# MCU_PFC161.net
KiCad netlist of a schematic drawn in Altium Designer
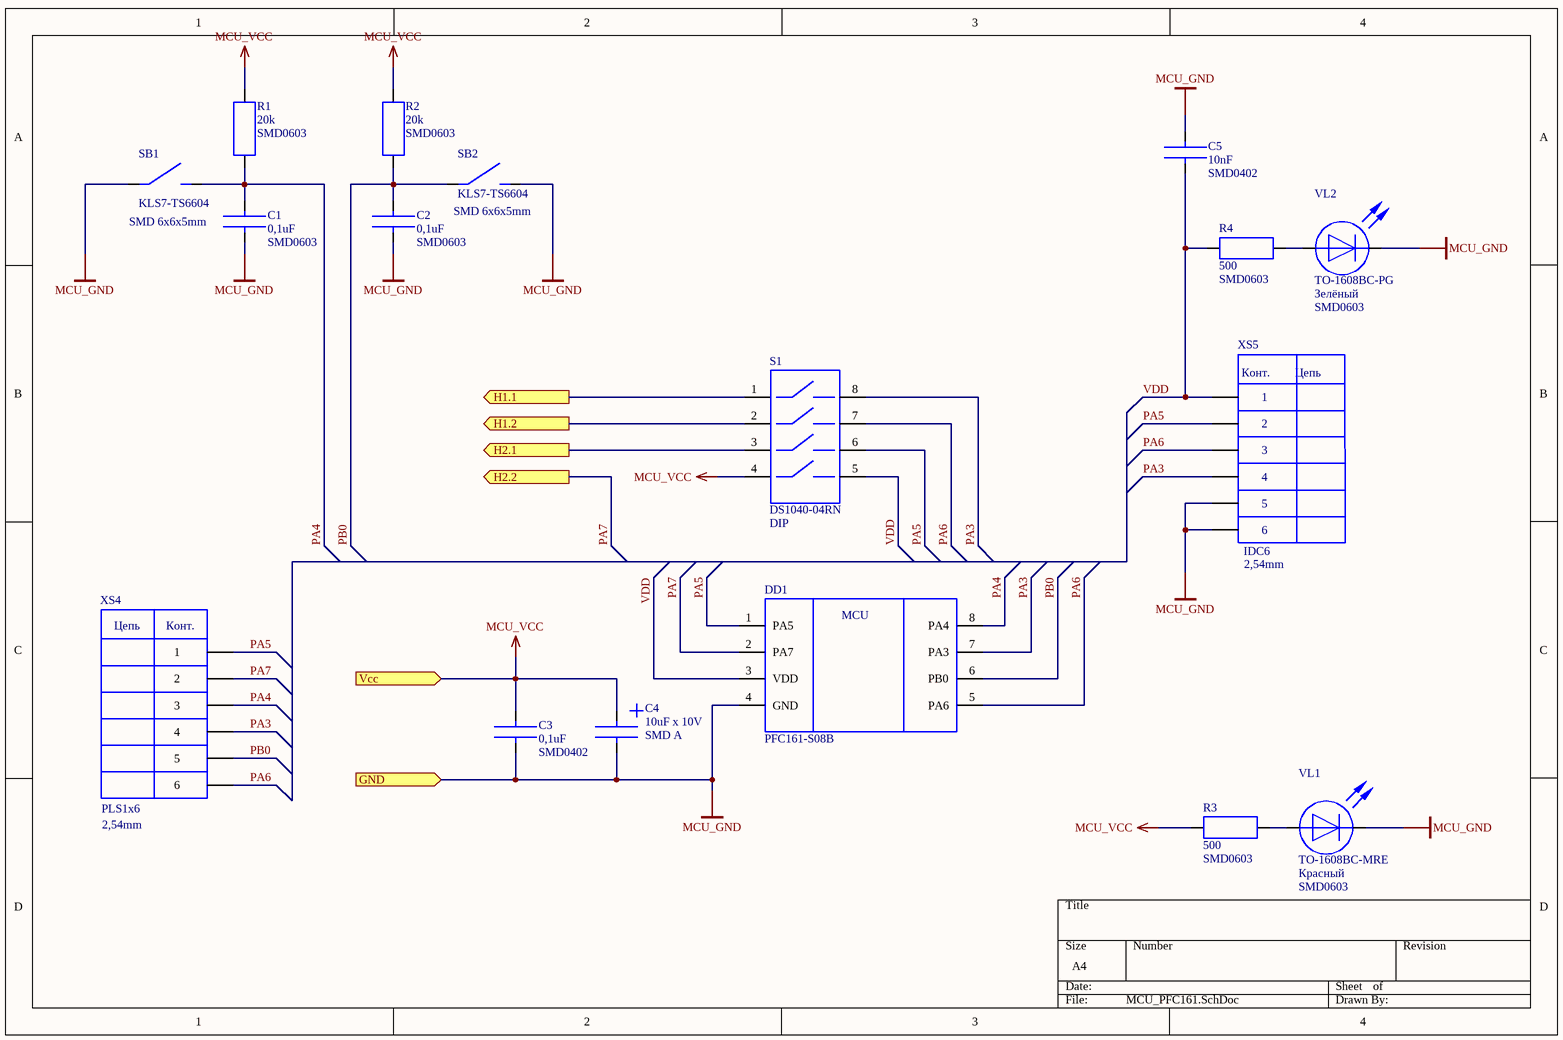
[diagram p0: MCU_PFC161.SchDoc]

(export (version "E")
  (design (tool "Eeschema 10.0.6"))
  (components
    (comp (ref "C1")
      (value "0,1uF")
      (footprint "SMD0603(1005)")
      (fields (field (name "PACKAGE") "SMD0603"))
      (libsource (lib "MechanikLibrary") (part "CER_CUP_0603"))
    )
    (comp (ref "C2")
      (value "0,1uF")
      (footprint "SMD0603(1005)")
      (fields (field (name "PACKAGE") "SMD0603"))
      (libsource (lib "MechanikLibrary") (part "CER_CUP_0603"))
    )
    (comp (ref "C3")
      (value "0,1uF")
      (footprint "SMD0402(1608)")
      (fields (field (name "PACKAGE") "SMD0402"))
      (libsource (lib "MechanikLibrary") (part "CER_CUP_0402"))
    )
    (comp (ref "C4")
      (value "10uF x 10V")
      (footprint "TANT_CAP_A(3216)")
      (fields (field (name "PACKAGE") "SMD A"))
      (libsource (lib "MechanikLibrary") (part "C_TANT_A"))
    )
    (comp (ref "C5")
      (value "10nF")
      (footprint "SMD0603(1005)")
      (fields (field (name "PACKAGE") "SMD0402"))
      (libsource (lib "MechanikLibrary") (part "CER_CUP_0402"))
    )
    (comp (ref "DD1")
      (value "PFC161-S08B")
      (footprint "SOIC8")
      (libsource (lib "MechanikLibrary") (part "PFC161-S08B"))
    )
    (comp (ref "R1")
      (value "20k")
      (footprint "SMD0603(1005)")
      (fields (field (name "PACKAGE") "SMD0603"))
      (libsource (lib "MechanikLibrary") (part "R_0603"))
    )
    (comp (ref "R2")
      (value "20k")
      (footprint "SMD0603(1005)")
      (fields (field (name "PACKAGE") "SMD0603"))
      (libsource (lib "MechanikLibrary") (part "R_0603"))
    )
    (comp (ref "R3")
      (value "500")
      (footprint "SMD0603(1005)")
      (fields (field (name "PACKAGE") "SMD0603"))
      (libsource (lib "MechanikLibrary") (part "R_0603"))
    )
    (comp (ref "R4")
      (value "500")
      (footprint "SMD0603(1005)")
      (fields (field (name "PACKAGE") "SMD0603"))
      (libsource (lib "MechanikLibrary") (part "R_0603"))
    )
    (comp (ref "S1")
      (value "DS1040-04RN")
      (footprint "DIP_SWITCH_4_2.54")
      (fields (field (name "PACKAGE") "DIP"))
      (libsource (lib "MechanikLibrary") (part "Переключатель DIP DS1040-04RN"))
    )
    (comp (ref "SB1")
      (value "KLS7-TS6604")
      (footprint "KLS7-TS6604 (IT-1102SA)")
      (fields (field (name "PACKAGE") "SMD 6х6х5mm"))
      (libsource (lib "MechanikLibrary") (part "Кнопка KLS7-TS6604 (IT-1102SA)"))
    )
    (comp (ref "SB2")
      (value "KLS7-TS6604")
      (footprint "KLS7-TS6604 (IT-1102SA)")
      (fields (field (name "PACKAGE") "SMD 6х6х5mm"))
      (libsource (lib "MechanikLibrary") (part "Кнопка KLS7-TS6604 (IT-1102SA)"))
    )
    (comp (ref "VL1")
      (value "TO-1608BC-MRE")
      (footprint "LED_SMD0603(1005)")
      (fields (field (name "LIGHT") "Красный") (field (name "PACKAGE") "SMD0603"))
      (libsource (lib "MechanikLibrary") (part "LED_0603"))
    )
    (comp (ref "VL2")
      (value "TO-1608BC-PG")
      (footprint "LED_SMD0603(1005)")
      (fields (field (name "LIGHT") "Зелёный") (field (name "PACKAGE") "SMD0603"))
      (libsource (lib "MechanikLibrary") (part "LED_0603"))
    )
    (comp (ref "XS4")
      (value "PLS1x6")
      (footprint "PLS1x6")
      (fields (field (name "PACKAGE") "2,54mm"))
      (libsource (lib "MechanikLibrary") (part "PLS1x6"))
    )
    (comp (ref "XS5")
      (value "IDC6")
      (footprint "IDC-6 (2.54)")
      (fields (field (name "PACKAGE") "2,54mm"))
      (libsource (lib "MechanikLibrary") (part "IDC6"))
    )
  )
  (nets
    (net (code "1") (name "/H1.1") (class "Default")
      (node (ref "S1") (pin "1") (pinfunction "1_1") (pintype "passive"))
    )
    (net (code "2") (name "/H1.2") (class "Default")
      (node (ref "S1") (pin "2") (pinfunction "2_2") (pintype "passive"))
    )
    (net (code "3") (name "/H2.1") (class "Default")
      (node (ref "S1") (pin "3") (pinfunction "3_3") (pintype "passive"))
    )
    (net (code "4") (name "/PA3") (class "Default")
      (node (ref "DD1") (pin "7") (pinfunction "PA3_7") (pintype "passive"))
      (node (ref "S1") (pin "8") (pinfunction "1_8") (pintype "passive"))
      (node (ref "XS4") (pin "4") (pinfunction "4_4") (pintype "passive"))
      (node (ref "XS5") (pin "4") (pintype "passive"))
    )
    (net (code "5") (name "/PA4") (class "Default")
      (node (ref "C1") (pin "2") (pintype "passive"))
      (node (ref "DD1") (pin "8") (pinfunction "PA4_8") (pintype "passive"))
      (node (ref "R1") (pin "1") (pintype "passive"))
      (node (ref "SB1") (pin "2") (pintype "passive"))
      (node (ref "XS4") (pin "3") (pinfunction "3_3") (pintype "passive"))
    )
    (net (code "6") (name "/PA5") (class "Default")
      (node (ref "DD1") (pin "1") (pinfunction "PA5_1") (pintype "passive"))
      (node (ref "S1") (pin "6") (pinfunction "3_6") (pintype "passive"))
      (node (ref "XS4") (pin "1") (pinfunction "1_1") (pintype "passive"))
      (node (ref "XS5") (pin "2") (pintype "passive"))
    )
    (net (code "7") (name "/PA6") (class "Default")
      (node (ref "DD1") (pin "5") (pinfunction "PA6_5") (pintype "passive"))
      (node (ref "S1") (pin "7") (pinfunction "2_7") (pintype "passive"))
      (node (ref "XS4") (pin "6") (pinfunction "6_6") (pintype "passive"))
      (node (ref "XS5") (pin "3") (pintype "passive"))
    )
    (net (code "8") (name "/PA7") (class "Default")
      (node (ref "DD1") (pin "2") (pinfunction "PA7_2") (pintype "passive"))
      (node (ref "XS4") (pin "2") (pinfunction "2_2") (pintype "passive"))
    )
    (net (code "9") (name "/PB0") (class "Default")
      (node (ref "C2") (pin "2") (pintype "passive"))
      (node (ref "DD1") (pin "6") (pinfunction "PB0_6") (pintype "passive"))
      (node (ref "R2") (pin "1") (pintype "passive"))
      (node (ref "SB2") (pin "1") (pintype "passive"))
      (node (ref "XS4") (pin "5") (pinfunction "5_5") (pintype "passive"))
    )
    (net (code "10") (name "/VDD") (class "Default")
      (node (ref "C5") (pin "2") (pintype "passive"))
      (node (ref "DD1") (pin "3") (pinfunction "VDD_3") (pintype "passive"))
      (node (ref "R4") (pin "1") (pintype "passive"))
      (node (ref "S1") (pin "5") (pinfunction "4_5") (pintype "passive"))
      (node (ref "XS5") (pin "1") (pintype "passive"))
    )
    (net (code "11") (name "MCU_GND") (class "Default")
      (node (ref "C1") (pin "1") (pintype "passive"))
      (node (ref "C2") (pin "1") (pintype "passive"))
      (node (ref "C3") (pin "2") (pintype "passive"))
      (node (ref "C4") (pin "2") (pintype "passive"))
      (node (ref "C5") (pin "1") (pintype "passive"))
      (node (ref "DD1") (pin "4") (pinfunction "GND_4") (pintype "passive"))
      (node (ref "SB1") (pin "1") (pintype "passive"))
      (node (ref "SB2") (pin "2") (pintype "passive"))
      (node (ref "VL1") (pin "2") (pintype "passive"))
      (node (ref "VL2") (pin "2") (pintype "passive"))
      (node (ref "XS5") (pin "5") (pintype "passive"))
      (node (ref "XS5") (pin "6") (pintype "passive"))
    )
    (net (code "12") (name "MCU_VCC") (class "Default")
      (node (ref "C3") (pin "1") (pintype "passive"))
      (node (ref "C4") (pin "1") (pintype "passive"))
      (node (ref "R1") (pin "2") (pintype "passive"))
      (node (ref "R2") (pin "2") (pintype "passive"))
      (node (ref "R3") (pin "1") (pintype "passive"))
      (node (ref "S1") (pin "4") (pinfunction "4_4") (pintype "passive"))
    )
    (net (code "13") (name "Net-(R3-Pad2)") (class "Default")
      (node (ref "R3") (pin "2") (pintype "passive"))
      (node (ref "VL1") (pin "1") (pintype "passive"))
    )
    (net (code "14") (name "Net-(R4-Pad2)") (class "Default")
      (node (ref "R4") (pin "2") (pintype "passive"))
      (node (ref "VL2") (pin "1") (pintype "passive"))
    )
  )
)
